# Sheet1.net
KiCad netlist of a schematic drawn in Altium Designer
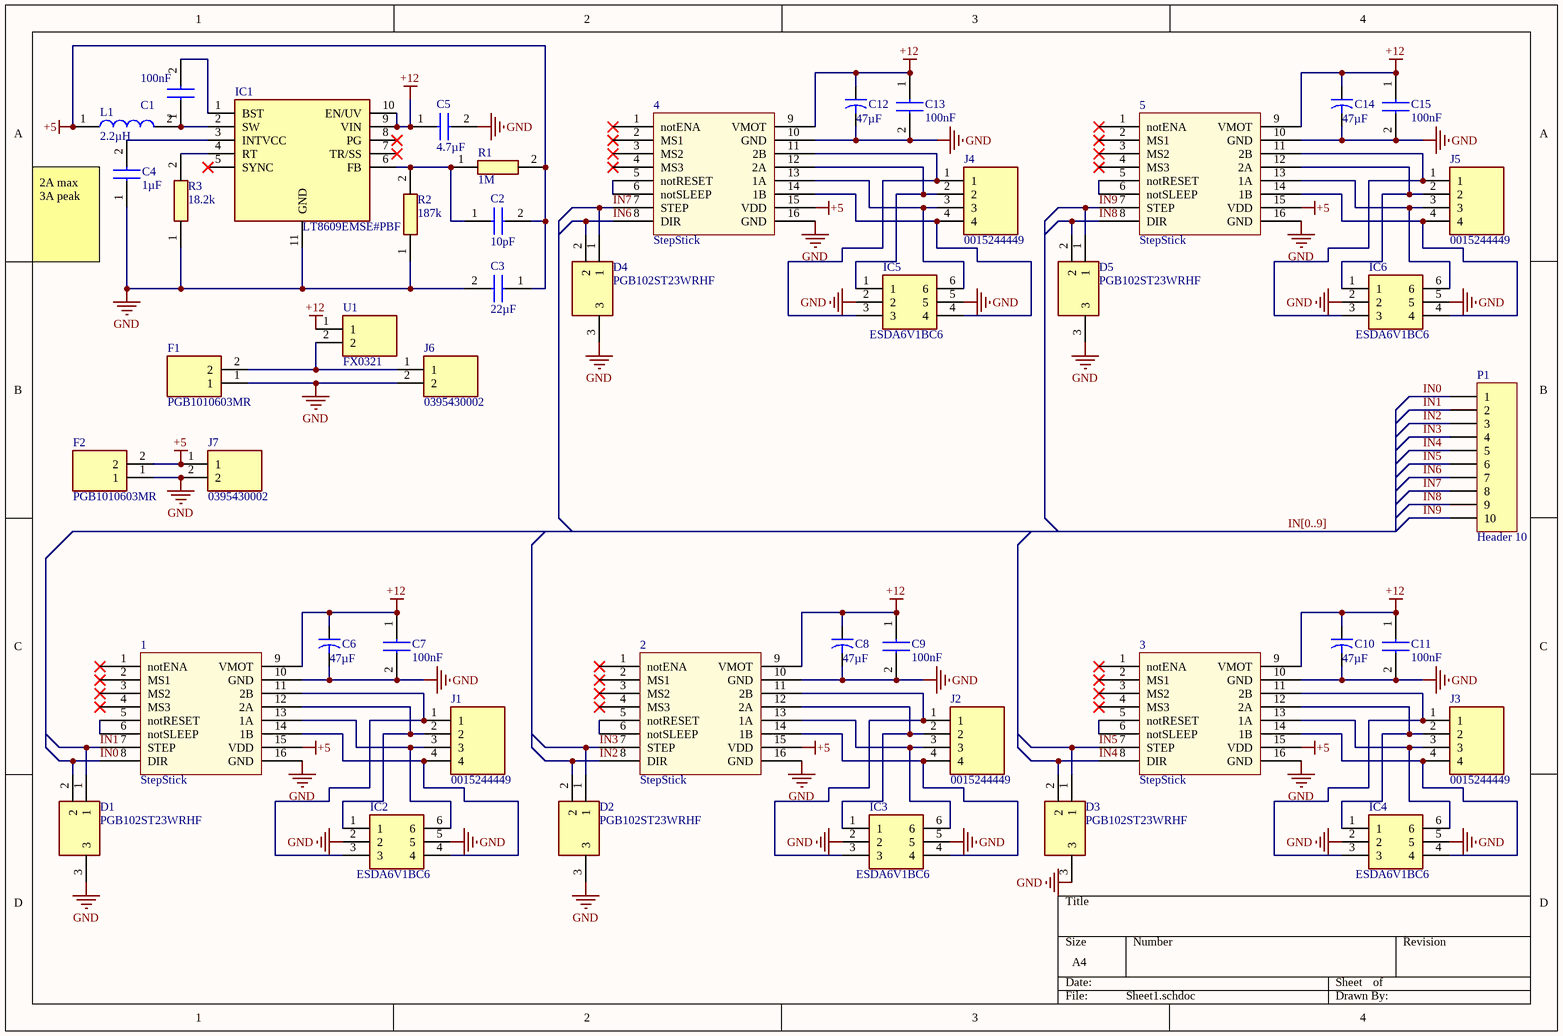
[diagram p0: Sheet1.schdoc]

(export (version "E")
  (design (tool "Eeschema 10.0.6"))
  (components
    (comp (ref "1")
      (value "StepStick")
      (footprint "StepStick")
      (libsource (lib "Schlib1") (part "StepStick"))
    )
    (comp (ref "2")
      (value "StepStick")
      (footprint "StepStick")
      (libsource (lib "Schlib1") (part "StepStick"))
    )
    (comp (ref "3")
      (value "StepStick")
      (footprint "StepStick")
      (libsource (lib "Schlib1") (part "StepStick"))
    )
    (comp (ref "4")
      (value "StepStick")
      (footprint "StepStick")
      (libsource (lib "Schlib1") (part "StepStick"))
    )
    (comp (ref "5")
      (value "StepStick")
      (footprint "StepStick")
      (libsource (lib "Schlib1") (part "StepStick"))
    )
    (comp (ref "C1")
      (value "100nF")
      (footprint "SamacSys:CAPC1608X95N")
      (description "Capacitor")
      (fields
        (field (name "MANUFACTURER_PART_NUMBER") "C0603C104K3RACTU")
        (field (name "MOUSER PART NUMBER") "80-C0603C104K3R")
      )
      (libsource (lib "*") (part "C0603C104K3RACTU"))
    )
    (comp (ref "C2")
      (value "10pF")
      (footprint "SamacSys:CAPC1608X95N")
      (description "Capacitor")
      (fields
        (field (name "MANUFACTURER_PART_NUMBER") "C0603C104K3RACTU")
        (field (name "MOUSER PART NUMBER") "80-C0603C104K3R")
      )
      (libsource (lib "*") (part "C0603C104K3RACTU"))
    )
    (comp (ref "C3")
      (value "22µF")
      (footprint "SamacSys:CAPC1608X95N")
      (description "Capacitor")
      (fields
        (field (name "MANUFACTURER_PART_NUMBER") "C0603C104K3RACTU")
        (field (name "MOUSER PART NUMBER") "80-C0603C104K3R")
      )
      (libsource (lib "*") (part "C0603C104K3RACTU"))
    )
    (comp (ref "C4")
      (value "1µF")
      (footprint "SamacSys:CAPC1608X95N")
      (description "Capacitor")
      (fields
        (field (name "MANUFACTURER_PART_NUMBER") "C0603C104K3RACTU")
        (field (name "MOUSER PART NUMBER") "80-C0603C104K3R")
      )
      (libsource (lib "*") (part "C0603C104K3RACTU"))
    )
    (comp (ref "C5")
      (value "4.7µF")
      (footprint "SamacSys:CAPC1608X95N")
      (description "Capacitor")
      (fields
        (field (name "MANUFACTURER_PART_NUMBER") "C0603C104K3RACTU")
        (field (name "MOUSER PART NUMBER") "80-C0603C104K3R")
      )
      (libsource (lib "*") (part "C0603C104K3RACTU"))
    )
    (comp (ref "C6")
      (value "47µF")
      (footprint "CAPR5-4X5")
      (description "Capacitor")
      (fields (field (name "PUBLISHER") "Altium Limited"))
      (libsource (lib "Miscellaneous Devices") (part "Cap2"))
    )
    (comp (ref "C7")
      (value "100nF")
      (footprint "SamacSys:CAPC0603X33N")
      (description "Capacitor")
      (fields
        (field (name "MANUFACTURER_PART_NUMBER") "02016D104KAT2A")
        (field (name "MOUSER PART NUMBER") "581-02016D104KAT2A")
      )
      (libsource (lib "*") (part "02016D104KAT2A"))
    )
    (comp (ref "C8")
      (value "47µF")
      (footprint "CAPR5-4X5")
      (description "Capacitor")
      (fields (field (name "PUBLISHER") "Altium Limited"))
      (libsource (lib "Miscellaneous Devices") (part "Cap2"))
    )
    (comp (ref "C9")
      (value "100nF")
      (footprint "SamacSys:CAPC0603X33N")
      (description "Capacitor")
      (fields
        (field (name "MANUFACTURER_PART_NUMBER") "02016D104KAT2A")
        (field (name "MOUSER PART NUMBER") "581-02016D104KAT2A")
      )
      (libsource (lib "*") (part "02016D104KAT2A"))
    )
    (comp (ref "C10")
      (value "47µF")
      (footprint "CAPR5-4X5")
      (description "Capacitor")
      (fields (field (name "PUBLISHER") "Altium Limited"))
      (libsource (lib "Miscellaneous Devices") (part "Cap2"))
    )
    (comp (ref "C11")
      (value "100nF")
      (footprint "SamacSys:CAPC0603X33N")
      (description "Capacitor")
      (fields
        (field (name "MANUFACTURER_PART_NUMBER") "02016D104KAT2A")
        (field (name "MOUSER PART NUMBER") "581-02016D104KAT2A")
      )
      (libsource (lib "*") (part "02016D104KAT2A"))
    )
    (comp (ref "C12")
      (value "47µF")
      (footprint "CAPR5-4X5")
      (description "Capacitor")
      (fields (field (name "PUBLISHER") "Altium Limited"))
      (libsource (lib "Miscellaneous Devices") (part "Cap2"))
    )
    (comp (ref "C13")
      (value "100nF")
      (footprint "SamacSys:CAPC0603X33N")
      (description "Capacitor")
      (fields
        (field (name "MANUFACTURER_PART_NUMBER") "02016D104KAT2A")
        (field (name "MOUSER PART NUMBER") "581-02016D104KAT2A")
      )
      (libsource (lib "*") (part "02016D104KAT2A"))
    )
    (comp (ref "C14")
      (value "47µF")
      (footprint "CAPR5-4X5")
      (description "Capacitor")
      (fields (field (name "PUBLISHER") "Altium Limited"))
      (libsource (lib "Miscellaneous Devices") (part "Cap2"))
    )
    (comp (ref "C15")
      (value "100nF")
      (footprint "SamacSys:CAPC0603X33N")
      (description "Capacitor")
      (fields
        (field (name "MANUFACTURER_PART_NUMBER") "02016D104KAT2A")
        (field (name "MOUSER PART NUMBER") "581-02016D104KAT2A")
      )
      (libsource (lib "*") (part "02016D104KAT2A"))
    )
    (comp (ref "D1")
      (value "PGB102ST23WRHF")
      (footprint "SamacSys:PGB102ST23WRHF")
      (description "Diode")
      (fields (field (name "MOUSER PART NUMBER") "576-PGB102ST23WRHF"))
      (libsource (lib "*") (part "PGB102ST23WRHF"))
    )
    (comp (ref "D2")
      (value "PGB102ST23WRHF")
      (footprint "SamacSys:PGB102ST23WRHF")
      (description "Diode")
      (fields (field (name "MOUSER PART NUMBER") "576-PGB102ST23WRHF"))
      (libsource (lib "*") (part "PGB102ST23WRHF"))
    )
    (comp (ref "D3")
      (value "PGB102ST23WRHF")
      (footprint "SamacSys:PGB102ST23WRHF")
      (description "Diode")
      (fields (field (name "MOUSER PART NUMBER") "576-PGB102ST23WRHF"))
      (libsource (lib "*") (part "PGB102ST23WRHF"))
    )
    (comp (ref "D4")
      (value "PGB102ST23WRHF")
      (footprint "SamacSys:PGB102ST23WRHF")
      (description "Diode")
      (fields (field (name "MOUSER PART NUMBER") "576-PGB102ST23WRHF"))
      (libsource (lib "*") (part "PGB102ST23WRHF"))
    )
    (comp (ref "D5")
      (value "PGB102ST23WRHF")
      (footprint "SamacSys:PGB102ST23WRHF")
      (description "Diode")
      (fields (field (name "MOUSER PART NUMBER") "576-PGB102ST23WRHF"))
      (libsource (lib "*") (part "PGB102ST23WRHF"))
    )
    (comp (ref "F1")
      (value "PGB1010603MR")
      (footprint "SamacSys:FUSC1708X36N")
      (description "Fuse")
      (fields
        (field (name "MOUSER PART NUMBER") "576-PGB1010603MR")
        (field (name "RS PART NUMBER") "7383191P")
      )
      (libsource (lib "*") (part "PGB1010603MR"))
    )
    (comp (ref "F2")
      (value "PGB1010603MR")
      (footprint "SamacSys:FUSC1708X36N")
      (description "Fuse")
      (fields
        (field (name "MOUSER PART NUMBER") "576-PGB1010603MR")
        (field (name "RS PART NUMBER") "7383191P")
      )
      (libsource (lib "*") (part "PGB1010603MR"))
    )
    (comp (ref "IC1")
      (value "LT8609EMSE#PBF")
      (footprint "SamacSys:SOP50P490X110-11N")
      (description "Integrated Circuit")
      (fields
        (field (name "MOUSER PART NUMBER") "584-LT8609EMSE#PBF")
        (field (name "RS PART NUMBER") "1646081P")
      )
      (libsource (lib "*") (part "LT8609EMSE#PBF"))
    )
    (comp (ref "IC2")
      (value "ESDA6V1BC6")
      (footprint "SamacSys:SOT95P280X145-6N")
      (description "Integrated Circuit")
      (fields (field (name "MOUSER PART NUMBER") "511-ESDA6V1BC6") (field (name "RS PART NUMBER") "0248805"))
      (libsource (lib "*") (part "ESDA6V1BC6"))
    )
    (comp (ref "IC3")
      (value "ESDA6V1BC6")
      (footprint "SamacSys:SOT95P280X145-6N")
      (description "Integrated Circuit")
      (fields (field (name "MOUSER PART NUMBER") "511-ESDA6V1BC6") (field (name "RS PART NUMBER") "0248805"))
      (libsource (lib "*") (part "ESDA6V1BC6"))
    )
    (comp (ref "IC4")
      (value "ESDA6V1BC6")
      (footprint "SamacSys:SOT95P280X145-6N")
      (description "Integrated Circuit")
      (fields (field (name "MOUSER PART NUMBER") "511-ESDA6V1BC6") (field (name "RS PART NUMBER") "0248805"))
      (libsource (lib "*") (part "ESDA6V1BC6"))
    )
    (comp (ref "IC5")
      (value "ESDA6V1BC6")
      (footprint "SamacSys:SOT95P280X145-6N")
      (description "Integrated Circuit")
      (fields (field (name "MOUSER PART NUMBER") "511-ESDA6V1BC6") (field (name "RS PART NUMBER") "0248805"))
      (libsource (lib "*") (part "ESDA6V1BC6"))
    )
    (comp (ref "IC6")
      (value "ESDA6V1BC6")
      (footprint "SamacSys:SOT95P280X145-6N")
      (description "Integrated Circuit")
      (fields (field (name "MOUSER PART NUMBER") "511-ESDA6V1BC6") (field (name "RS PART NUMBER") "0248805"))
      (libsource (lib "*") (part "ESDA6V1BC6"))
    )
    (comp (ref "J1")
      (value "0015244449")
      (footprint "SamacSys:0015244449")
      (description "Connector")
      (libsource (lib "*") (part "0015244449"))
    )
    (comp (ref "J2")
      (value "0015244449")
      (footprint "SamacSys:0015244449")
      (description "Connector")
      (libsource (lib "*") (part "0015244449"))
    )
    (comp (ref "J3")
      (value "0015244449")
      (footprint "SamacSys:0015244449")
      (description "Connector")
      (libsource (lib "*") (part "0015244449"))
    )
    (comp (ref "J4")
      (value "0015244449")
      (footprint "SamacSys:0015244449")
      (description "Connector")
      (libsource (lib "*") (part "0015244449"))
    )
    (comp (ref "J5")
      (value "0015244449")
      (footprint "SamacSys:0015244449")
      (description "Connector")
      (libsource (lib "*") (part "0015244449"))
    )
    (comp (ref "J6")
      (value "0395430002")
      (footprint "SamacSys:SHDR2W100P0X500_1X2_1000X950X1490P")
      (description "Connector")
      (libsource (lib "*") (part "0395430002"))
    )
    (comp (ref "J7")
      (value "0395430002")
      (footprint "SamacSys:SHDR2W100P0X500_1X2_1000X950X1490P")
      (description "Connector")
      (libsource (lib "*") (part "0395430002"))
    )
    (comp (ref "L1")
      (value "2.2µH")
      (footprint "SamacSys:WE-TPC_8015/801292")
      (description "Inductor")
      (fields
        (field (name "MANUFACTURER_PART_NUMBER") "7440680150")
        (field (name "MOUSER PART NUMBER") "710-7440680150")
      )
      (libsource (lib "*") (part "7440680150"))
    )
    (comp (ref "P1")
      (value "Header 10")
      (footprint "HDR1X10")
      (description "Header, 10-Pin")
      (fields (field (name "PUBLISHER") "Altium Limited"))
      (libsource (lib "Miscellaneous Connectors") (part "Header 10"))
    )
    (comp (ref "R1")
      (value "1M")
      (footprint "SamacSys:RESC1608X55N")
      (description "Resistor")
      (fields
        (field (name "MANUFACTURER_PART_NUMBER") "CR0603-FX-1004ELF")
        (field (name "MOUSER PART NUMBER") "652-CR0603FX-1004ELF")
      )
      (libsource (lib "") (part "CR0603-FX-1004ELF_1"))
    )
    (comp (ref "R2")
      (value "187k")
      (footprint "SamacSys:RESC1608X55N")
      (description "Resistor")
      (fields
        (field (name "MANUFACTURER_PART_NUMBER") "CR0603-FX-1004ELF")
        (field (name "MOUSER PART NUMBER") "652-CR0603FX-1004ELF")
      )
      (libsource (lib "*") (part "CR0603-FX-1004ELF"))
    )
    (comp (ref "R3")
      (value "18.2k")
      (footprint "SamacSys:RESC1608X55N")
      (description "Resistor")
      (fields
        (field (name "MANUFACTURER_PART_NUMBER") "CR0603-FX-1004ELF")
        (field (name "MOUSER PART NUMBER") "652-CR0603FX-1004ELF")
      )
      (libsource (lib "*") (part "CR0603-FX-1004ELF"))
    )
    (comp (ref "U1")
      (value "FX0321")
      (footprint "SamacSys:FX0321")
      (description "Undefined or Miscellaneous")
      (fields (field (name "MOUSER PART NUMBER") "422-FX0321") (field (name "RS PART NUMBER") "0417098"))
      (libsource (lib "*") (part "FX0321"))
    )
  )
  (nets
    (net (code "1") (name "+5") (class "Default")
      (node (ref "1") (pin "15") (pinfunction "VDD_15") (pintype "passive"))
      (node (ref "2") (pin "15") (pinfunction "VDD_15") (pintype "passive"))
      (node (ref "3") (pin "15") (pinfunction "VDD_15") (pintype "passive"))
      (node (ref "4") (pin "15") (pinfunction "VDD_15") (pintype "passive"))
      (node (ref "5") (pin "15") (pinfunction "VDD_15") (pintype "passive"))
      (node (ref "C2") (pin "2") (pinfunction "2_2") (pintype "passive"))
      (node (ref "C3") (pin "1") (pinfunction "1_1") (pintype "passive"))
      (node (ref "F2") (pin "2") (pinfunction "2_2") (pintype "passive"))
      (node (ref "J7") (pin "1") (pinfunction "1_1") (pintype "passive"))
      (node (ref "L1") (pin "1") (pinfunction "1_1") (pintype "passive"))
      (node (ref "R1") (pin "2") (pinfunction "2_2") (pintype "passive"))
    )
    (net (code "2") (name "+12") (class "Default")
      (node (ref "1") (pin "9") (pinfunction "VMOT_9") (pintype "passive"))
      (node (ref "2") (pin "9") (pinfunction "VMOT_9") (pintype "passive"))
      (node (ref "3") (pin "9") (pinfunction "VMOT_9") (pintype "passive"))
      (node (ref "4") (pin "9") (pinfunction "VMOT_9") (pintype "passive"))
      (node (ref "5") (pin "9") (pinfunction "VMOT_9") (pintype "passive"))
      (node (ref "C10") (pin "1") (pinfunction "1_1") (pintype "passive"))
      (node (ref "C11") (pin "1") (pinfunction "1_1") (pintype "passive"))
      (node (ref "C12") (pin "1") (pinfunction "1_1") (pintype "passive"))
      (node (ref "C13") (pin "1") (pinfunction "1_1") (pintype "passive"))
      (node (ref "C14") (pin "1") (pinfunction "1_1") (pintype "passive"))
      (node (ref "C15") (pin "1") (pinfunction "1_1") (pintype "passive"))
      (node (ref "C5") (pin "1") (pinfunction "1_1") (pintype "passive"))
      (node (ref "C6") (pin "1") (pinfunction "1_1") (pintype "passive"))
      (node (ref "C7") (pin "1") (pinfunction "1_1") (pintype "passive"))
      (node (ref "C8") (pin "1") (pinfunction "1_1") (pintype "passive"))
      (node (ref "C9") (pin "1") (pinfunction "1_1") (pintype "passive"))
      (node (ref "IC1") (pin "10") (pinfunction "EN/UV_10") (pintype "passive"))
      (node (ref "IC1") (pin "9") (pinfunction "VIN_9") (pintype "passive"))
      (node (ref "U1") (pin "1") (pinfunction "1_1") (pintype "passive"))
    )
    (net (code "3") (name "/IN0") (class "Default")
      (node (ref "1") (pin "8") (pinfunction "DIR_8") (pintype "passive"))
      (node (ref "D1") (pin "2") (pinfunction "2_2") (pintype "passive"))
      (node (ref "P1") (pin "1") (pinfunction "1_1") (pintype "passive"))
    )
    (net (code "4") (name "/IN1") (class "Default")
      (node (ref "1") (pin "7") (pinfunction "STEP_7") (pintype "passive"))
      (node (ref "D1") (pin "1") (pinfunction "1_1") (pintype "passive"))
      (node (ref "P1") (pin "2") (pinfunction "2_2") (pintype "passive"))
    )
    (net (code "5") (name "/IN2") (class "Default")
      (node (ref "2") (pin "8") (pinfunction "DIR_8") (pintype "passive"))
      (node (ref "D2") (pin "2") (pinfunction "2_2") (pintype "passive"))
      (node (ref "P1") (pin "3") (pinfunction "3_3") (pintype "passive"))
    )
    (net (code "6") (name "/IN3") (class "Default")
      (node (ref "2") (pin "7") (pinfunction "STEP_7") (pintype "passive"))
      (node (ref "D2") (pin "1") (pinfunction "1_1") (pintype "passive"))
      (node (ref "P1") (pin "4") (pinfunction "4_4") (pintype "passive"))
    )
    (net (code "7") (name "/IN4") (class "Default")
      (node (ref "3") (pin "8") (pinfunction "DIR_8") (pintype "passive"))
      (node (ref "D3") (pin "2") (pinfunction "2_2") (pintype "passive"))
      (node (ref "P1") (pin "5") (pinfunction "5_5") (pintype "passive"))
    )
    (net (code "8") (name "/IN5") (class "Default")
      (node (ref "3") (pin "7") (pinfunction "STEP_7") (pintype "passive"))
      (node (ref "D3") (pin "1") (pinfunction "1_1") (pintype "passive"))
      (node (ref "P1") (pin "6") (pinfunction "6_6") (pintype "passive"))
    )
    (net (code "9") (name "/IN6") (class "Default")
      (node (ref "4") (pin "8") (pinfunction "DIR_8") (pintype "passive"))
      (node (ref "D4") (pin "2") (pinfunction "2_2") (pintype "passive"))
      (node (ref "P1") (pin "7") (pinfunction "7_7") (pintype "passive"))
    )
    (net (code "10") (name "/IN7") (class "Default")
      (node (ref "4") (pin "7") (pinfunction "STEP_7") (pintype "passive"))
      (node (ref "D4") (pin "1") (pinfunction "1_1") (pintype "passive"))
      (node (ref "P1") (pin "8") (pinfunction "8_8") (pintype "passive"))
    )
    (net (code "11") (name "/IN8") (class "Default")
      (node (ref "5") (pin "8") (pinfunction "DIR_8") (pintype "passive"))
      (node (ref "D5") (pin "2") (pinfunction "2_2") (pintype "passive"))
      (node (ref "P1") (pin "9") (pinfunction "9_9") (pintype "passive"))
    )
    (net (code "12") (name "/IN9") (class "Default")
      (node (ref "5") (pin "7") (pinfunction "STEP_7") (pintype "passive"))
      (node (ref "D5") (pin "1") (pinfunction "1_1") (pintype "passive"))
      (node (ref "P1") (pin "10") (pinfunction "10_10") (pintype "passive"))
    )
    (net (code "14") (name "GND") (class "Default")
      (node (ref "1") (pin "10") (pinfunction "GND_10") (pintype "passive"))
      (node (ref "1") (pin "16") (pinfunction "GND_16") (pintype "passive"))
      (node (ref "2") (pin "10") (pinfunction "GND_10") (pintype "passive"))
      (node (ref "2") (pin "16") (pinfunction "GND_16") (pintype "passive"))
      (node (ref "3") (pin "10") (pinfunction "GND_10") (pintype "passive"))
      (node (ref "3") (pin "16") (pinfunction "GND_16") (pintype "passive"))
      (node (ref "4") (pin "10") (pinfunction "GND_10") (pintype "passive"))
      (node (ref "4") (pin "16") (pinfunction "GND_16") (pintype "passive"))
      (node (ref "5") (pin "10") (pinfunction "GND_10") (pintype "passive"))
      (node (ref "5") (pin "16") (pinfunction "GND_16") (pintype "passive"))
      (node (ref "C10") (pin "2") (pinfunction "2_2") (pintype "passive"))
      (node (ref "C11") (pin "2") (pinfunction "2_2") (pintype "passive"))
      (node (ref "C12") (pin "2") (pinfunction "2_2") (pintype "passive"))
      (node (ref "C13") (pin "2") (pinfunction "2_2") (pintype "passive"))
      (node (ref "C14") (pin "2") (pinfunction "2_2") (pintype "passive"))
      (node (ref "C15") (pin "2") (pinfunction "2_2") (pintype "passive"))
      (node (ref "C3") (pin "2") (pinfunction "2_2") (pintype "passive"))
      (node (ref "C4") (pin "1") (pinfunction "1_1") (pintype "passive"))
      (node (ref "C5") (pin "2") (pinfunction "2_2") (pintype "passive"))
      (node (ref "C6") (pin "2") (pinfunction "2_2") (pintype "passive"))
      (node (ref "C7") (pin "2") (pinfunction "2_2") (pintype "passive"))
      (node (ref "C8") (pin "2") (pinfunction "2_2") (pintype "passive"))
      (node (ref "C9") (pin "2") (pinfunction "2_2") (pintype "passive"))
      (node (ref "D1") (pin "3") (pinfunction "3_3") (pintype "passive"))
      (node (ref "D2") (pin "3") (pinfunction "3_3") (pintype "passive"))
      (node (ref "D3") (pin "3") (pinfunction "3_3") (pintype "passive"))
      (node (ref "D4") (pin "3") (pinfunction "3_3") (pintype "passive"))
      (node (ref "D5") (pin "3") (pinfunction "3_3") (pintype "passive"))
      (node (ref "F1") (pin "1") (pinfunction "1_1") (pintype "passive"))
      (node (ref "F2") (pin "1") (pinfunction "1_1") (pintype "passive"))
      (node (ref "IC1") (pin "11") (pinfunction "GND_11") (pintype "passive"))
      (node (ref "IC2") (pin "2") (pinfunction "2_2") (pintype "passive"))
      (node (ref "IC2") (pin "5") (pinfunction "5_5") (pintype "passive"))
      (node (ref "IC3") (pin "2") (pinfunction "2_2") (pintype "passive"))
      (node (ref "IC3") (pin "5") (pinfunction "5_5") (pintype "passive"))
      (node (ref "IC4") (pin "2") (pinfunction "2_2") (pintype "passive"))
      (node (ref "IC4") (pin "5") (pinfunction "5_5") (pintype "passive"))
      (node (ref "IC5") (pin "2") (pinfunction "2_2") (pintype "passive"))
      (node (ref "IC5") (pin "5") (pinfunction "5_5") (pintype "passive"))
      (node (ref "IC6") (pin "2") (pinfunction "2_2") (pintype "passive"))
      (node (ref "IC6") (pin "5") (pinfunction "5_5") (pintype "passive"))
      (node (ref "J6") (pin "2") (pinfunction "2_2") (pintype "passive"))
      (node (ref "J7") (pin "2") (pinfunction "2_2") (pintype "passive"))
      (node (ref "R2") (pin "1") (pinfunction "1_1") (pintype "passive"))
      (node (ref "R3") (pin "1") (pinfunction "1_1") (pintype "passive"))
    )
    (net (code "15") (name "Net-(1-1A)") (class "Default")
      (node (ref "1") (pin "13") (pinfunction "1A_13") (pintype "passive"))
      (node (ref "IC2") (pin "6") (pinfunction "6_6") (pintype "passive"))
      (node (ref "J1") (pin "3") (pinfunction "3_3") (pintype "passive"))
    )
    (net (code "16") (name "Net-(1-1B)") (class "Default")
      (node (ref "1") (pin "14") (pinfunction "1B_14") (pintype "passive"))
      (node (ref "IC2") (pin "4") (pinfunction "4_4") (pintype "passive"))
      (node (ref "J1") (pin "4") (pinfunction "4_4") (pintype "passive"))
    )
    (net (code "17") (name "Net-(1-2A)") (class "Default")
      (node (ref "1") (pin "12") (pinfunction "2A_12") (pintype "passive"))
      (node (ref "IC2") (pin "1") (pinfunction "1_1") (pintype "passive"))
      (node (ref "J1") (pin "2") (pinfunction "2_2") (pintype "passive"))
    )
    (net (code "18") (name "Net-(1-2B)") (class "Default")
      (node (ref "1") (pin "11") (pinfunction "2B_11") (pintype "passive"))
      (node (ref "IC2") (pin "3") (pinfunction "3_3") (pintype "passive"))
      (node (ref "J1") (pin "1") (pinfunction "1_1") (pintype "passive"))
    )
    (net (code "19") (name "Net-(1-notRESET)") (class "Default")
      (node (ref "1") (pin "5") (pinfunction "notRESET_5") (pintype "passive"))
      (node (ref "1") (pin "6") (pinfunction "notSLEEP_6") (pintype "passive"))
    )
    (net (code "20") (name "Net-(2-1A)") (class "Default")
      (node (ref "2") (pin "13") (pinfunction "1A_13") (pintype "passive"))
      (node (ref "IC3") (pin "6") (pinfunction "6_6") (pintype "passive"))
      (node (ref "J2") (pin "3") (pinfunction "3_3") (pintype "passive"))
    )
    (net (code "21") (name "Net-(2-1B)") (class "Default")
      (node (ref "2") (pin "14") (pinfunction "1B_14") (pintype "passive"))
      (node (ref "IC3") (pin "4") (pinfunction "4_4") (pintype "passive"))
      (node (ref "J2") (pin "4") (pinfunction "4_4") (pintype "passive"))
    )
    (net (code "22") (name "Net-(2-2A)") (class "Default")
      (node (ref "2") (pin "12") (pinfunction "2A_12") (pintype "passive"))
      (node (ref "IC3") (pin "1") (pinfunction "1_1") (pintype "passive"))
      (node (ref "J2") (pin "2") (pinfunction "2_2") (pintype "passive"))
    )
    (net (code "23") (name "Net-(2-2B)") (class "Default")
      (node (ref "2") (pin "11") (pinfunction "2B_11") (pintype "passive"))
      (node (ref "IC3") (pin "3") (pinfunction "3_3") (pintype "passive"))
      (node (ref "J2") (pin "1") (pinfunction "1_1") (pintype "passive"))
    )
    (net (code "24") (name "Net-(2-notRESET)") (class "Default")
      (node (ref "2") (pin "5") (pinfunction "notRESET_5") (pintype "passive"))
      (node (ref "2") (pin "6") (pinfunction "notSLEEP_6") (pintype "passive"))
    )
    (net (code "25") (name "Net-(3-1A)") (class "Default")
      (node (ref "3") (pin "13") (pinfunction "1A_13") (pintype "passive"))
      (node (ref "IC4") (pin "6") (pinfunction "6_6") (pintype "passive"))
      (node (ref "J3") (pin "3") (pinfunction "3_3") (pintype "passive"))
    )
    (net (code "26") (name "Net-(3-1B)") (class "Default")
      (node (ref "3") (pin "14") (pinfunction "1B_14") (pintype "passive"))
      (node (ref "IC4") (pin "4") (pinfunction "4_4") (pintype "passive"))
      (node (ref "J3") (pin "4") (pinfunction "4_4") (pintype "passive"))
    )
    (net (code "27") (name "Net-(3-2A)") (class "Default")
      (node (ref "3") (pin "12") (pinfunction "2A_12") (pintype "passive"))
      (node (ref "IC4") (pin "1") (pinfunction "1_1") (pintype "passive"))
      (node (ref "J3") (pin "2") (pinfunction "2_2") (pintype "passive"))
    )
    (net (code "28") (name "Net-(3-2B)") (class "Default")
      (node (ref "3") (pin "11") (pinfunction "2B_11") (pintype "passive"))
      (node (ref "IC4") (pin "3") (pinfunction "3_3") (pintype "passive"))
      (node (ref "J3") (pin "1") (pinfunction "1_1") (pintype "passive"))
    )
    (net (code "29") (name "Net-(3-notRESET)") (class "Default")
      (node (ref "3") (pin "5") (pinfunction "notRESET_5") (pintype "passive"))
      (node (ref "3") (pin "6") (pinfunction "notSLEEP_6") (pintype "passive"))
    )
    (net (code "30") (name "Net-(4-1A)") (class "Default")
      (node (ref "4") (pin "13") (pinfunction "1A_13") (pintype "passive"))
      (node (ref "IC5") (pin "6") (pinfunction "6_6") (pintype "passive"))
      (node (ref "J4") (pin "3") (pinfunction "3_3") (pintype "passive"))
    )
    (net (code "31") (name "Net-(4-1B)") (class "Default")
      (node (ref "4") (pin "14") (pinfunction "1B_14") (pintype "passive"))
      (node (ref "IC5") (pin "4") (pinfunction "4_4") (pintype "passive"))
      (node (ref "J4") (pin "4") (pinfunction "4_4") (pintype "passive"))
    )
    (net (code "32") (name "Net-(4-2A)") (class "Default")
      (node (ref "4") (pin "12") (pinfunction "2A_12") (pintype "passive"))
      (node (ref "IC5") (pin "1") (pinfunction "1_1") (pintype "passive"))
      (node (ref "J4") (pin "2") (pinfunction "2_2") (pintype "passive"))
    )
    (net (code "33") (name "Net-(4-2B)") (class "Default")
      (node (ref "4") (pin "11") (pinfunction "2B_11") (pintype "passive"))
      (node (ref "IC5") (pin "3") (pinfunction "3_3") (pintype "passive"))
      (node (ref "J4") (pin "1") (pinfunction "1_1") (pintype "passive"))
    )
    (net (code "34") (name "Net-(4-notRESET)") (class "Default")
      (node (ref "4") (pin "5") (pinfunction "notRESET_5") (pintype "passive"))
      (node (ref "4") (pin "6") (pinfunction "notSLEEP_6") (pintype "passive"))
    )
    (net (code "35") (name "Net-(5-1A)") (class "Default")
      (node (ref "5") (pin "13") (pinfunction "1A_13") (pintype "passive"))
      (node (ref "IC6") (pin "6") (pinfunction "6_6") (pintype "passive"))
      (node (ref "J5") (pin "3") (pinfunction "3_3") (pintype "passive"))
    )
    (net (code "36") (name "Net-(5-1B)") (class "Default")
      (node (ref "5") (pin "14") (pinfunction "1B_14") (pintype "passive"))
      (node (ref "IC6") (pin "4") (pinfunction "4_4") (pintype "passive"))
      (node (ref "J5") (pin "4") (pinfunction "4_4") (pintype "passive"))
    )
    (net (code "37") (name "Net-(5-2A)") (class "Default")
      (node (ref "5") (pin "12") (pinfunction "2A_12") (pintype "passive"))
      (node (ref "IC6") (pin "1") (pinfunction "1_1") (pintype "passive"))
      (node (ref "J5") (pin "2") (pinfunction "2_2") (pintype "passive"))
    )
    (net (code "38") (name "Net-(5-2B)") (class "Default")
      (node (ref "5") (pin "11") (pinfunction "2B_11") (pintype "passive"))
      (node (ref "IC6") (pin "3") (pinfunction "3_3") (pintype "passive"))
      (node (ref "J5") (pin "1") (pinfunction "1_1") (pintype "passive"))
    )
    (net (code "39") (name "Net-(5-notRESET)") (class "Default")
      (node (ref "5") (pin "5") (pinfunction "notRESET_5") (pintype "passive"))
      (node (ref "5") (pin "6") (pinfunction "notSLEEP_6") (pintype "passive"))
    )
    (net (code "40") (name "Net-(F1-Pad2)") (class "Default")
      (node (ref "F1") (pin "2") (pinfunction "2_2") (pintype "passive"))
      (node (ref "J6") (pin "1") (pinfunction "1_1") (pintype "passive"))
      (node (ref "U1") (pin "2") (pinfunction "2_2") (pintype "passive"))
    )
    (net (code "41") (name "Net-(IC1-BST)") (class "Default")
      (node (ref "C1") (pin "2") (pinfunction "2_2") (pintype "passive"))
      (node (ref "IC1") (pin "1") (pinfunction "BST_1") (pintype "passive"))
    )
    (net (code "42") (name "Net-(IC1-FB)") (class "Default")
      (node (ref "C2") (pin "1") (pinfunction "1_1") (pintype "passive"))
      (node (ref "IC1") (pin "6") (pinfunction "FB_6") (pintype "passive"))
      (node (ref "R1") (pin "1") (pinfunction "1_1") (pintype "passive"))
      (node (ref "R2") (pin "2") (pinfunction "2_2") (pintype "passive"))
    )
    (net (code "43") (name "Net-(IC1-INTVCC)") (class "Default")
      (node (ref "C4") (pin "2") (pinfunction "2_2") (pintype "passive"))
      (node (ref "IC1") (pin "3") (pinfunction "INTVCC_3") (pintype "passive"))
    )
    (net (code "44") (name "Net-(IC1-RT)") (class "Default")
      (node (ref "IC1") (pin "4") (pinfunction "RT_4") (pintype "passive"))
      (node (ref "R3") (pin "2") (pinfunction "2_2") (pintype "passive"))
    )
    (net (code "45") (name "Net-(IC1-SW)") (class "Default")
      (node (ref "C1") (pin "1") (pinfunction "1_1") (pintype "passive"))
      (node (ref "IC1") (pin "2") (pinfunction "SW_2") (pintype "passive"))
      (node (ref "L1") (pin "2") (pinfunction "2_2") (pintype "passive"))
    )
    (net (code "46") (name "unconnected-(1-MS1-Pad2)") (class "Default")
      (node (ref "1") (pin "2") (pinfunction "MS1_2") (pintype "passive+no_connect"))
    )
    (net (code "47") (name "unconnected-(1-MS2-Pad3)") (class "Default")
      (node (ref "1") (pin "3") (pinfunction "MS2_3") (pintype "passive+no_connect"))
    )
    (net (code "48") (name "unconnected-(1-MS3-Pad4)") (class "Default")
      (node (ref "1") (pin "4") (pinfunction "MS3_4") (pintype "passive+no_connect"))
    )
    (net (code "49") (name "unconnected-(1-notENA-Pad1)") (class "Default")
      (node (ref "1") (pin "1") (pinfunction "notENA_1") (pintype "passive+no_connect"))
    )
    (net (code "50") (name "unconnected-(2-MS1-Pad2)") (class "Default")
      (node (ref "2") (pin "2") (pinfunction "MS1_2") (pintype "passive+no_connect"))
    )
    (net (code "51") (name "unconnected-(2-MS2-Pad3)") (class "Default")
      (node (ref "2") (pin "3") (pinfunction "MS2_3") (pintype "passive+no_connect"))
    )
    (net (code "52") (name "unconnected-(2-MS3-Pad4)") (class "Default")
      (node (ref "2") (pin "4") (pinfunction "MS3_4") (pintype "passive+no_connect"))
    )
    (net (code "53") (name "unconnected-(2-notENA-Pad1)") (class "Default")
      (node (ref "2") (pin "1") (pinfunction "notENA_1") (pintype "passive+no_connect"))
    )
    (net (code "54") (name "unconnected-(3-MS1-Pad2)") (class "Default")
      (node (ref "3") (pin "2") (pinfunction "MS1_2") (pintype "passive+no_connect"))
    )
    (net (code "55") (name "unconnected-(3-MS2-Pad3)") (class "Default")
      (node (ref "3") (pin "3") (pinfunction "MS2_3") (pintype "passive+no_connect"))
    )
    (net (code "56") (name "unconnected-(3-MS3-Pad4)") (class "Default")
      (node (ref "3") (pin "4") (pinfunction "MS3_4") (pintype "passive+no_connect"))
    )
    (net (code "57") (name "unconnected-(3-notENA-Pad1)") (class "Default")
      (node (ref "3") (pin "1") (pinfunction "notENA_1") (pintype "passive+no_connect"))
    )
    (net (code "58") (name "unconnected-(4-MS1-Pad2)") (class "Default")
      (node (ref "4") (pin "2") (pinfunction "MS1_2") (pintype "passive+no_connect"))
    )
    (net (code "59") (name "unconnected-(4-MS2-Pad3)") (class "Default")
      (node (ref "4") (pin "3") (pinfunction "MS2_3") (pintype "passive+no_connect"))
    )
    (net (code "60") (name "unconnected-(4-MS3-Pad4)") (class "Default")
      (node (ref "4") (pin "4") (pinfunction "MS3_4") (pintype "passive+no_connect"))
    )
    (net (code "61") (name "unconnected-(4-notENA-Pad1)") (class "Default")
      (node (ref "4") (pin "1") (pinfunction "notENA_1") (pintype "passive+no_connect"))
    )
    (net (code "62") (name "unconnected-(5-MS1-Pad2)") (class "Default")
      (node (ref "5") (pin "2") (pinfunction "MS1_2") (pintype "passive+no_connect"))
    )
    (net (code "63") (name "unconnected-(5-MS2-Pad3)") (class "Default")
      (node (ref "5") (pin "3") (pinfunction "MS2_3") (pintype "passive+no_connect"))
    )
    (net (code "64") (name "unconnected-(5-MS3-Pad4)") (class "Default")
      (node (ref "5") (pin "4") (pinfunction "MS3_4") (pintype "passive+no_connect"))
    )
    (net (code "65") (name "unconnected-(5-notENA-Pad1)") (class "Default")
      (node (ref "5") (pin "1") (pinfunction "notENA_1") (pintype "passive+no_connect"))
    )
    (net (code "66") (name "unconnected-(IC1-PG-Pad8)") (class "Default")
      (node (ref "IC1") (pin "8") (pinfunction "PG_8") (pintype "passive+no_connect"))
    )
    (net (code "67") (name "unconnected-(IC1-SYNC-Pad5)") (class "Default")
      (node (ref "IC1") (pin "5") (pinfunction "SYNC_5") (pintype "passive+no_connect"))
    )
    (net (code "68") (name "unconnected-(IC1-TR{slash}SS-Pad7)") (class "Default")
      (node (ref "IC1") (pin "7") (pinfunction "TR/SS_7") (pintype "passive+no_connect"))
    )
  )
)
